# STM32Fx.net
KiCad netlist of a schematic drawn in Altium Designer
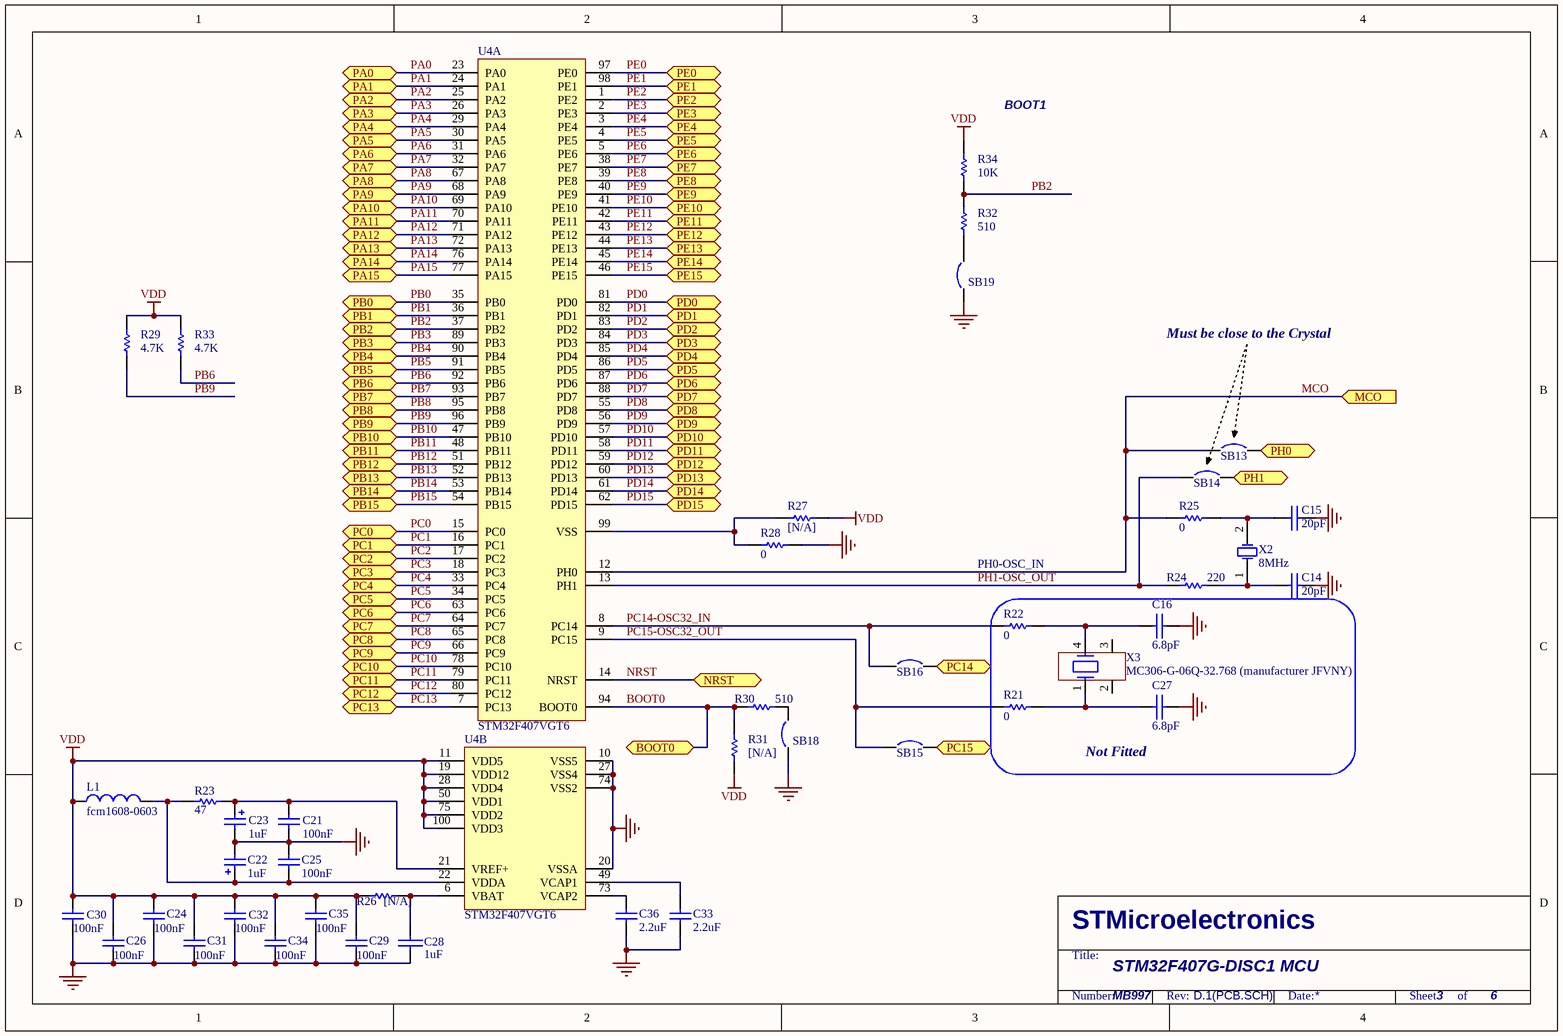
[diagram p0: STM32Fx.SchDoc]

(export (version "E")
  (design (tool "Eeschema 10.0.6"))
  (components
    (comp (ref "C14")
      (value "20pF")
      (footprint "0603C")
      (description "Capacitor")
      (libsource (lib "") (part "CAP_1"))
    )
    (comp (ref "C15")
      (value "20pF")
      (footprint "0603C")
      (description "Capacitor")
      (libsource (lib "") (part "CAP_1"))
    )
    (comp (ref "C16")
      (value "6.8pF")
      (footprint "0603C")
      (description "Capacitor")
      (libsource (lib "*") (part "CAP"))
    )
    (comp (ref "C21")
      (value "100nF")
      (footprint "0603C")
      (description "Capacitor")
      (fields (field (name "PUBLISHER") "Altium Limited"))
      (libsource (lib "MB915_1") (part "Cap"))
    )
    (comp (ref "C22")
      (value "1uF")
      (footprint "CASE-AA")
      (description "Polarized Capacitor (Radial)")
      (fields (field (name "PUBLISHER") "Altium Limited"))
      (libsource (lib "Miscellaneous Devices") (part "Cap Pol1"))
    )
    (comp (ref "C23")
      (value "1uF")
      (footprint "CASE-AA")
      (description "Polarized Capacitor (Radial)")
      (fields (field (name "PUBLISHER") "Altium Limited"))
      (libsource (lib "Miscellaneous Devices") (part "Cap Pol1"))
    )
    (comp (ref "C24")
      (value "100nF")
      (footprint "0603C")
      (description "Capacitor")
      (fields (field (name "PUBLISHER") "Altium Limited"))
      (libsource (lib "MB915_1") (part "Cap"))
    )
    (comp (ref "C25")
      (value "100nF")
      (footprint "0603C")
      (description "Capacitor")
      (fields (field (name "PUBLISHER") "Altium Limited"))
      (libsource (lib "MB915_1") (part "Cap"))
    )
    (comp (ref "C26")
      (value "100nF")
      (footprint "0603C")
      (description "Capacitor")
      (fields (field (name "PUBLISHER") "Altium Limited"))
      (libsource (lib "MB915_1") (part "Cap"))
    )
    (comp (ref "C27")
      (value "6.8pF")
      (footprint "0603C")
      (description "Capacitor")
      (libsource (lib "*") (part "CAP"))
    )
    (comp (ref "C28")
      (value "1uF")
      (footprint "0603C")
      (description "Capacitor")
      (libsource (lib "") (part "CAP_1"))
    )
    (comp (ref "C29")
      (value "100nF")
      (footprint "0603C")
      (description "Capacitor")
      (fields (field (name "PUBLISHER") "Altium Limited"))
      (libsource (lib "MB915_1") (part "Cap"))
    )
    (comp (ref "C30")
      (value "100nF")
      (footprint "0603C")
      (description "Capacitor")
      (fields (field (name "PUBLISHER") "Altium Limited"))
      (libsource (lib "MB915_1") (part "Cap"))
    )
    (comp (ref "C31")
      (value "100nF")
      (footprint "0603C")
      (description "Capacitor")
      (fields (field (name "PUBLISHER") "Altium Limited"))
      (libsource (lib "MB915_1") (part "Cap"))
    )
    (comp (ref "C32")
      (value "100nF")
      (footprint "0603C")
      (description "Capacitor")
      (fields (field (name "PUBLISHER") "Altium Limited"))
      (libsource (lib "MB915_1") (part "Cap"))
    )
    (comp (ref "C33")
      (value "2.2uF")
      (footprint "CASE-A")
      (description "Low ESR Ceramic Capacitor (X7R)")
      (fields (field (name "PUBLISHER") "Altium Limited"))
      (libsource (lib "MB997") (part "Cap Low ESR"))
    )
    (comp (ref "C34")
      (value "100nF")
      (footprint "0603C")
      (description "Capacitor")
      (fields (field (name "PUBLISHER") "Altium Limited"))
      (libsource (lib "MB915_1") (part "Cap"))
    )
    (comp (ref "C35")
      (value "100nF")
      (footprint "0603C")
      (description "Capacitor")
      (fields (field (name "PUBLISHER") "Altium Limited"))
      (libsource (lib "MB915_1") (part "Cap"))
    )
    (comp (ref "C36")
      (value "2.2uF")
      (footprint "CASE-A")
      (description "Low ESR Ceramic Capacitor (X7R)")
      (fields (field (name "PUBLISHER") "Altium Limited"))
      (libsource (lib "MB997") (part "Cap Low ESR"))
    )
    (comp (ref "L1")
      (value "fcm1608-0603")
      (footprint "0603L")
      (description "Inductor")
      (fields (field (name "PUBLISHER") "Altium Limited"))
      (libsource (lib "Miscellaneous Devices") (part "Inductor"))
    )
    (comp (ref "R21")
      (value "0")
      (footprint "0603R")
      (description "Resistor")
      (fields (field (name "PUBLISHER") "Altium Limited"))
      (libsource (lib "Miscellaneous Devices") (part "Res1"))
    )
    (comp (ref "R22")
      (value "0")
      (footprint "0603R")
      (description "Resistor")
      (fields (field (name "PUBLISHER") "Altium Limited"))
      (libsource (lib "Miscellaneous Devices") (part "Res1"))
    )
    (comp (ref "R23")
      (value "47")
      (footprint "0603R")
      (description "Resistor")
      (fields (field (name "PUBLISHER") "Altium Limited"))
      (libsource (lib "Miscellaneous Devices") (part "Res1"))
    )
    (comp (ref "R24")
      (value "220")
      (footprint "0603R")
      (description "Resistor")
      (fields (field (name "PUBLISHER") "Altium Limited"))
      (libsource (lib "Miscellaneous Devices") (part "Res1"))
    )
    (comp (ref "R25")
      (value "0")
      (footprint "0603R")
      (description "Resistor")
      (fields (field (name "PUBLISHER") "Altium Limited"))
      (libsource (lib "Miscellaneous Devices") (part "Res1"))
    )
    (comp (ref "R26")
      (value "[N/A]")
      (footprint "0603R")
      (description "Resistor")
      (fields (field (name "PUBLISHER") "Altium Limited"))
      (libsource (lib "Miscellaneous Devices") (part "res1"))
    )
    (comp (ref "R27")
      (value "[N/A]")
      (footprint "0603R")
      (description "Resistor")
      (fields (field (name "PUBLISHER") "Altium Limited"))
      (libsource (lib "Miscellaneous Devices") (part "Res1"))
    )
    (comp (ref "R28")
      (value "0")
      (footprint "0603R")
      (description "Resistor")
      (fields (field (name "PUBLISHER") "Altium Limited"))
      (libsource (lib "Miscellaneous Devices") (part "Res1"))
    )
    (comp (ref "R29")
      (value "4.7K")
      (footprint "0402R")
      (description "Resistor")
      (fields (field (name "PUBLISHER") "Altium Limited"))
      (libsource (lib "Miscellaneous Devices") (part "res1"))
    )
    (comp (ref "R30")
      (value "510")
      (footprint "0603R")
      (description "Resistor")
      (fields (field (name "PUBLISHER") "Altium Limited"))
      (libsource (lib "Miscellaneous Devices") (part "Res1"))
    )
    (comp (ref "R31")
      (value "[N/A]")
      (footprint "0402R")
      (description "Resistor")
      (fields (field (name "PUBLISHER") "Altium Limited"))
      (libsource (lib "Miscellaneous Devices") (part "res1"))
    )
    (comp (ref "R32")
      (value "510")
      (footprint "0603R")
      (description "Resistor")
      (fields (field (name "PUBLISHER") "Altium Limited"))
      (libsource (lib "Miscellaneous Devices") (part "res1"))
    )
    (comp (ref "R33")
      (value "4.7K")
      (footprint "0402R")
      (description "Resistor")
      (fields (field (name "PUBLISHER") "Altium Limited"))
      (libsource (lib "Miscellaneous Devices") (part "res1"))
    )
    (comp (ref "R34")
      (value "10K")
      (footprint "0402R")
      (description "Resistor")
      (fields (field (name "PUBLISHER") "Altium Limited"))
      (libsource (lib "Miscellaneous Devices") (part "res1"))
    )
    (comp (ref "SB13")
      (value "Circuit Breaker")
      (footprint "JP2_SMD")
      (fields (field (name "PUBLISHER") "Altium Limited"))
      (libsource (lib "MB915") (part "Circuit Breaker"))
    )
    (comp (ref "SB14")
      (value "Circuit Breaker")
      (footprint "JP2_SMD")
      (fields (field (name "PUBLISHER") "Altium Limited"))
      (libsource (lib "MB915") (part "Circuit Breaker"))
    )
    (comp (ref "SB15")
      (value "Circuit Breaker")
      (footprint "JP2_SMD")
      (fields (field (name "PUBLISHER") "Altium Limited"))
      (libsource (lib "MB915") (part "Circuit Breaker"))
    )
    (comp (ref "SB16")
      (value "Circuit Breaker")
      (footprint "JP2_SMD")
      (fields (field (name "PUBLISHER") "Altium Limited"))
      (libsource (lib "MB915") (part "Circuit Breaker"))
    )
    (comp (ref "SB18")
      (value "Circuit Breaker")
      (footprint "JP2_SMD")
      (fields (field (name "PUBLISHER") "Altium Limited"))
      (libsource (lib "MB915") (part "Circuit Breaker"))
    )
    (comp (ref "SB19")
      (value "Circuit Breaker")
      (footprint "JP2_SMD")
      (fields (field (name "PUBLISHER") "Altium Limited"))
      (libsource (lib "MB915") (part "Circuit Breaker"))
    )
    (comp (ref "U4")
      (value "STM32F407VGT6")
      (footprint "TQFP100")
      (description "STM32 Manta (STM32F407VGT6)")
      (libsource (lib "MCD_TOOLS") (part "STM32F407VGT6"))
    )
    (comp (ref "X2")
      (value "8MHz")
      (footprint "XTAL1")
      (description "Crystal Oscillator")
      (fields (field (name "PUBLISHER") "Altium Limited"))
      (libsource (lib "MB963_1") (part "XTAL"))
    )
    (comp (ref "X3")
      (value "MC306-G-06Q-32.768 (manufacturer JFVNY)")
      (footprint "MC306-CRYSTAL")
      (libsource (lib "*") (part "MC306"))
    )
  )
  (nets
    (net (code "1") (name "/BOOT0") (class "Default")
      (node (ref "R30") (pin "2") (pinfunction "2_2") (pintype "passive"))
      (node (ref "R31") (pin "1") (pinfunction "1_1") (pintype "passive"))
      (node (ref "U4") (pin "94") (pinfunction "BOOT0_94") (pintype "passive"))
    )
    (net (code "2") (name "/MCO") (class "Default")
      (node (ref "R25") (pin "1") (pinfunction "1_1") (pintype "passive"))
      (node (ref "SB13") (pin "1") (pinfunction "1_1") (pintype "passive"))
      (node (ref "U4") (pin "12") (pinfunction "PH0_12") (pintype "passive"))
    )
    (net (code "3") (name "/NRST") (class "Default")
      (node (ref "U4") (pin "14") (pinfunction "NRST_14") (pintype "passive"))
    )
    (net (code "4") (name "/PA0") (class "Default")
      (node (ref "U4") (pin "23") (pinfunction "PA0_23") (pintype "passive"))
    )
    (net (code "5") (name "/PA1") (class "Default")
      (node (ref "U4") (pin "24") (pinfunction "PA1_24") (pintype "passive"))
    )
    (net (code "6") (name "/PA2") (class "Default")
      (node (ref "U4") (pin "25") (pinfunction "PA2_25") (pintype "passive"))
    )
    (net (code "7") (name "/PA3") (class "Default")
      (node (ref "U4") (pin "26") (pinfunction "PA3_26") (pintype "passive"))
    )
    (net (code "8") (name "/PA4") (class "Default")
      (node (ref "U4") (pin "29") (pinfunction "PA4_29") (pintype "passive"))
    )
    (net (code "9") (name "/PA5") (class "Default")
      (node (ref "U4") (pin "30") (pinfunction "PA5_30") (pintype "passive"))
    )
    (net (code "10") (name "/PA6") (class "Default")
      (node (ref "U4") (pin "31") (pinfunction "PA6_31") (pintype "passive"))
    )
    (net (code "11") (name "/PA7") (class "Default")
      (node (ref "U4") (pin "32") (pinfunction "PA7_32") (pintype "passive"))
    )
    (net (code "12") (name "/PA8") (class "Default")
      (node (ref "U4") (pin "67") (pinfunction "PA8_67") (pintype "passive"))
    )
    (net (code "13") (name "/PA9") (class "Default")
      (node (ref "U4") (pin "68") (pinfunction "PA9_68") (pintype "passive"))
    )
    (net (code "14") (name "/PA10") (class "Default")
      (node (ref "U4") (pin "69") (pinfunction "PA10_69") (pintype "passive"))
    )
    (net (code "15") (name "/PA11") (class "Default")
      (node (ref "U4") (pin "70") (pinfunction "PA11_70") (pintype "passive"))
    )
    (net (code "16") (name "/PA12") (class "Default")
      (node (ref "U4") (pin "71") (pinfunction "PA12_71") (pintype "passive"))
    )
    (net (code "17") (name "/PA13") (class "Default")
      (node (ref "U4") (pin "72") (pinfunction "PA13_72") (pintype "passive"))
    )
    (net (code "18") (name "/PA14") (class "Default")
      (node (ref "U4") (pin "76") (pinfunction "PA14_76") (pintype "passive"))
    )
    (net (code "19") (name "/PA15") (class "Default")
      (node (ref "U4") (pin "77") (pinfunction "PA15_77") (pintype "passive"))
    )
    (net (code "20") (name "/PB0") (class "Default")
      (node (ref "U4") (pin "35") (pinfunction "PB0_35") (pintype "passive"))
    )
    (net (code "21") (name "/PB1") (class "Default")
      (node (ref "U4") (pin "36") (pinfunction "PB1_36") (pintype "passive"))
    )
    (net (code "22") (name "/PB2") (class "Default")
      (node (ref "R32") (pin "1") (pinfunction "1_1") (pintype "passive"))
      (node (ref "R34") (pin "2") (pinfunction "2_2") (pintype "passive"))
      (node (ref "U4") (pin "37") (pinfunction "PB2_37") (pintype "passive"))
    )
    (net (code "23") (name "/PB3") (class "Default")
      (node (ref "U4") (pin "89") (pinfunction "PB3_89") (pintype "passive"))
    )
    (net (code "24") (name "/PB4") (class "Default")
      (node (ref "U4") (pin "90") (pinfunction "PB4_90") (pintype "passive"))
    )
    (net (code "25") (name "/PB5") (class "Default")
      (node (ref "U4") (pin "91") (pinfunction "PB5_91") (pintype "passive"))
    )
    (net (code "26") (name "/PB6") (class "Default")
      (node (ref "R33") (pin "2") (pinfunction "2_2") (pintype "passive"))
      (node (ref "U4") (pin "92") (pinfunction "PB6_92") (pintype "passive"))
    )
    (net (code "27") (name "/PB7") (class "Default")
      (node (ref "U4") (pin "93") (pinfunction "PB7_93") (pintype "passive"))
    )
    (net (code "28") (name "/PB8") (class "Default")
      (node (ref "U4") (pin "95") (pinfunction "PB8_95") (pintype "passive"))
    )
    (net (code "29") (name "/PB9") (class "Default")
      (node (ref "R29") (pin "2") (pinfunction "2_2") (pintype "passive"))
      (node (ref "U4") (pin "96") (pinfunction "PB9_96") (pintype "passive"))
    )
    (net (code "30") (name "/PB10") (class "Default")
      (node (ref "U4") (pin "47") (pinfunction "PB10_47") (pintype "passive"))
    )
    (net (code "31") (name "/PB11") (class "Default")
      (node (ref "U4") (pin "48") (pinfunction "PB11_48") (pintype "passive"))
    )
    (net (code "32") (name "/PB12") (class "Default")
      (node (ref "U4") (pin "51") (pinfunction "PB12_51") (pintype "passive"))
    )
    (net (code "33") (name "/PB13") (class "Default")
      (node (ref "U4") (pin "52") (pinfunction "PB13_52") (pintype "passive"))
    )
    (net (code "34") (name "/PB14") (class "Default")
      (node (ref "U4") (pin "53") (pinfunction "PB14_53") (pintype "passive"))
    )
    (net (code "35") (name "/PB15") (class "Default")
      (node (ref "U4") (pin "54") (pinfunction "PB15_54") (pintype "passive"))
    )
    (net (code "36") (name "/PC0") (class "Default")
      (node (ref "U4") (pin "15") (pinfunction "PC0_15") (pintype "passive"))
    )
    (net (code "37") (name "/PC1") (class "Default")
      (node (ref "U4") (pin "16") (pinfunction "PC1_16") (pintype "passive"))
    )
    (net (code "38") (name "/PC2") (class "Default")
      (node (ref "U4") (pin "17") (pinfunction "PC2_17") (pintype "passive"))
    )
    (net (code "39") (name "/PC3") (class "Default")
      (node (ref "U4") (pin "18") (pinfunction "PC3_18") (pintype "passive"))
    )
    (net (code "40") (name "/PC4") (class "Default")
      (node (ref "U4") (pin "33") (pinfunction "PC4_33") (pintype "passive"))
    )
    (net (code "41") (name "/PC5") (class "Default")
      (node (ref "U4") (pin "34") (pinfunction "PC5_34") (pintype "passive"))
    )
    (net (code "42") (name "/PC6") (class "Default")
      (node (ref "U4") (pin "63") (pinfunction "PC6_63") (pintype "passive"))
    )
    (net (code "43") (name "/PC7") (class "Default")
      (node (ref "U4") (pin "64") (pinfunction "PC7_64") (pintype "passive"))
    )
    (net (code "44") (name "/PC8") (class "Default")
      (node (ref "U4") (pin "65") (pinfunction "PC8_65") (pintype "passive"))
    )
    (net (code "45") (name "/PC9") (class "Default")
      (node (ref "U4") (pin "66") (pinfunction "PC9_66") (pintype "passive"))
    )
    (net (code "46") (name "/PC10") (class "Default")
      (node (ref "U4") (pin "78") (pinfunction "PC10_78") (pintype "passive"))
    )
    (net (code "47") (name "/PC11") (class "Default")
      (node (ref "U4") (pin "79") (pinfunction "PC11_79") (pintype "passive"))
    )
    (net (code "48") (name "/PC12") (class "Default")
      (node (ref "U4") (pin "80") (pinfunction "PC12_80") (pintype "passive"))
    )
    (net (code "49") (name "/PC13") (class "Default")
      (node (ref "U4") (pin "7") (pinfunction "PC13_7") (pintype "passive"))
    )
    (net (code "50") (name "/PC14") (class "Default")
      (node (ref "SB16") (pin "2") (pinfunction "2_2") (pintype "passive"))
    )
    (net (code "51") (name "/PC14-OSC32_IN") (class "Default")
      (node (ref "R22") (pin "1") (pinfunction "1_1") (pintype "passive"))
      (node (ref "SB16") (pin "1") (pinfunction "1_1") (pintype "passive"))
      (node (ref "U4") (pin "8") (pinfunction "PC14_8") (pintype "passive"))
    )
    (net (code "52") (name "/PC15") (class "Default")
      (node (ref "SB15") (pin "2") (pinfunction "2_2") (pintype "passive"))
    )
    (net (code "53") (name "/PC15-OSC32_OUT") (class "Default")
      (node (ref "R21") (pin "1") (pinfunction "1_1") (pintype "passive"))
      (node (ref "SB15") (pin "1") (pinfunction "1_1") (pintype "passive"))
      (node (ref "U4") (pin "9") (pinfunction "PC15_9") (pintype "passive"))
    )
    (net (code "54") (name "/PD0") (class "Default")
      (node (ref "U4") (pin "81") (pinfunction "PD0_81") (pintype "passive"))
    )
    (net (code "55") (name "/PD1") (class "Default")
      (node (ref "U4") (pin "82") (pinfunction "PD1_82") (pintype "passive"))
    )
    (net (code "56") (name "/PD2") (class "Default")
      (node (ref "U4") (pin "83") (pinfunction "PD2_83") (pintype "passive"))
    )
    (net (code "57") (name "/PD3") (class "Default")
      (node (ref "U4") (pin "84") (pinfunction "PD3_84") (pintype "passive"))
    )
    (net (code "58") (name "/PD4") (class "Default")
      (node (ref "U4") (pin "85") (pinfunction "PD4_85") (pintype "passive"))
    )
    (net (code "59") (name "/PD5") (class "Default")
      (node (ref "U4") (pin "86") (pinfunction "PD5_86") (pintype "passive"))
    )
    (net (code "60") (name "/PD6") (class "Default")
      (node (ref "U4") (pin "87") (pinfunction "PD6_87") (pintype "passive"))
    )
    (net (code "61") (name "/PD7") (class "Default")
      (node (ref "U4") (pin "88") (pinfunction "PD7_88") (pintype "passive"))
    )
    (net (code "62") (name "/PD8") (class "Default")
      (node (ref "U4") (pin "55") (pinfunction "PD8_55") (pintype "passive"))
    )
    (net (code "63") (name "/PD9") (class "Default")
      (node (ref "U4") (pin "56") (pinfunction "PD9_56") (pintype "passive"))
    )
    (net (code "64") (name "/PD10") (class "Default")
      (node (ref "U4") (pin "57") (pinfunction "PD10_57") (pintype "passive"))
    )
    (net (code "65") (name "/PD11") (class "Default")
      (node (ref "U4") (pin "58") (pinfunction "PD11_58") (pintype "passive"))
    )
    (net (code "66") (name "/PD12") (class "Default")
      (node (ref "U4") (pin "59") (pinfunction "PD12_59") (pintype "passive"))
    )
    (net (code "67") (name "/PD13") (class "Default")
      (node (ref "U4") (pin "60") (pinfunction "PD13_60") (pintype "passive"))
    )
    (net (code "68") (name "/PD14") (class "Default")
      (node (ref "U4") (pin "61") (pinfunction "PD14_61") (pintype "passive"))
    )
    (net (code "69") (name "/PD15") (class "Default")
      (node (ref "U4") (pin "62") (pinfunction "PD15_62") (pintype "passive"))
    )
    (net (code "70") (name "/PE0") (class "Default")
      (node (ref "U4") (pin "97") (pinfunction "PE0_97") (pintype "passive"))
    )
    (net (code "71") (name "/PE1") (class "Default")
      (node (ref "U4") (pin "98") (pinfunction "PE1_98") (pintype "passive"))
    )
    (net (code "72") (name "/PE2") (class "Default")
      (node (ref "U4") (pin "1") (pinfunction "PE2_1") (pintype "passive"))
    )
    (net (code "73") (name "/PE3") (class "Default")
      (node (ref "U4") (pin "2") (pinfunction "PE3_2") (pintype "passive"))
    )
    (net (code "74") (name "/PE4") (class "Default")
      (node (ref "U4") (pin "3") (pinfunction "PE4_3") (pintype "passive"))
    )
    (net (code "75") (name "/PE5") (class "Default")
      (node (ref "U4") (pin "4") (pinfunction "PE5_4") (pintype "passive"))
    )
    (net (code "76") (name "/PE6") (class "Default")
      (node (ref "U4") (pin "5") (pinfunction "PE6_5") (pintype "passive"))
    )
    (net (code "77") (name "/PE7") (class "Default")
      (node (ref "U4") (pin "38") (pinfunction "PE7_38") (pintype "passive"))
    )
    (net (code "78") (name "/PE8") (class "Default")
      (node (ref "U4") (pin "39") (pinfunction "PE8_39") (pintype "passive"))
    )
    (net (code "79") (name "/PE9") (class "Default")
      (node (ref "U4") (pin "40") (pinfunction "PE9_40") (pintype "passive"))
    )
    (net (code "80") (name "/PE10") (class "Default")
      (node (ref "U4") (pin "41") (pinfunction "PE10_41") (pintype "passive"))
    )
    (net (code "81") (name "/PE11") (class "Default")
      (node (ref "U4") (pin "42") (pinfunction "PE11_42") (pintype "passive"))
    )
    (net (code "82") (name "/PE12") (class "Default")
      (node (ref "U4") (pin "43") (pinfunction "PE12_43") (pintype "passive"))
    )
    (net (code "83") (name "/PE13") (class "Default")
      (node (ref "U4") (pin "44") (pinfunction "PE13_44") (pintype "passive"))
    )
    (net (code "84") (name "/PE14") (class "Default")
      (node (ref "U4") (pin "45") (pinfunction "PE14_45") (pintype "passive"))
    )
    (net (code "85") (name "/PE15") (class "Default")
      (node (ref "U4") (pin "46") (pinfunction "PE15_46") (pintype "passive"))
    )
    (net (code "86") (name "/PH0") (class "Default")
      (node (ref "SB13") (pin "2") (pinfunction "2_2") (pintype "passive"))
    )
    (net (code "87") (name "/PH1") (class "Default")
      (node (ref "SB14") (pin "2") (pinfunction "2_2") (pintype "passive"))
    )
    (net (code "88") (name "/PH1-OSC_OUT") (class "Default")
      (node (ref "R24") (pin "2") (pinfunction "2_2") (pintype "passive"))
      (node (ref "SB14") (pin "1") (pinfunction "1_1") (pintype "passive"))
      (node (ref "U4") (pin "13") (pinfunction "PH1_13") (pintype "passive"))
    )
    (net (code "89") (name "GND") (class "Default")
      (node (ref "C14") (pin "1") (pinfunction "1_1") (pintype "passive"))
      (node (ref "C15") (pin "1") (pinfunction "1_1") (pintype "passive"))
      (node (ref "C16") (pin "2") (pinfunction "2_2") (pintype "passive"))
      (node (ref "C21") (pin "1") (pinfunction "1_1") (pintype "passive"))
      (node (ref "C22") (pin "2") (pinfunction "2_2") (pintype "passive"))
      (node (ref "C23") (pin "2") (pinfunction "2_2") (pintype "passive"))
      (node (ref "C24") (pin "2") (pinfunction "2_2") (pintype "passive"))
      (node (ref "C25") (pin "1") (pinfunction "1_1") (pintype "passive"))
      (node (ref "C26") (pin "1") (pinfunction "1_1") (pintype "passive"))
      (node (ref "C27") (pin "2") (pinfunction "2_2") (pintype "passive"))
      (node (ref "C28") (pin "2") (pinfunction "2_2") (pintype "passive"))
      (node (ref "C29") (pin "1") (pinfunction "1_1") (pintype "passive"))
      (node (ref "C30") (pin "1") (pinfunction "1_1") (pintype "passive"))
      (node (ref "C31") (pin "1") (pinfunction "1_1") (pintype "passive"))
      (node (ref "C32") (pin "1") (pinfunction "1_1") (pintype "passive"))
      (node (ref "C33") (pin "2") (pinfunction "2_2") (pintype "passive"))
      (node (ref "C34") (pin "1") (pinfunction "1_1") (pintype "passive"))
      (node (ref "C35") (pin "2") (pinfunction "2_2") (pintype "passive"))
      (node (ref "C36") (pin "2") (pinfunction "2_2") (pintype "passive"))
      (node (ref "R28") (pin "2") (pinfunction "2_2") (pintype "passive"))
      (node (ref "SB18") (pin "1") (pinfunction "1_1") (pintype "passive"))
      (node (ref "SB19") (pin "1") (pinfunction "1_1") (pintype "passive"))
      (node (ref "U4") (pin "10") (pinfunction "VSS5_10") (pintype "passive"))
      (node (ref "U4") (pin "20") (pinfunction "VSSA_20") (pintype "passive"))
      (node (ref "U4") (pin "27") (pinfunction "VSS4_27") (pintype "passive"))
      (node (ref "U4") (pin "74") (pinfunction "VSS2_74") (pintype "passive"))
    )
    (net (code "90") (name "Net-(C16-Pad1)") (class "Default")
      (node (ref "C16") (pin "1") (pinfunction "1_1") (pintype "passive"))
      (node (ref "R22") (pin "2") (pinfunction "2_2") (pintype "passive"))
      (node (ref "X3") (pin "4") (pinfunction "4_4") (pintype "passive"))
    )
    (net (code "91") (name "Net-(C27-Pad1)") (class "Default")
      (node (ref "C27") (pin "1") (pinfunction "1_1") (pintype "passive"))
      (node (ref "R21") (pin "2") (pinfunction "2_2") (pintype "passive"))
      (node (ref "X3") (pin "1") (pinfunction "1_1") (pintype "passive"))
    )
    (net (code "92") (name "Net-(R30-Pad1)") (class "Default")
      (node (ref "R30") (pin "1") (pinfunction "1_1") (pintype "passive"))
      (node (ref "SB18") (pin "2") (pinfunction "2_2") (pintype "passive"))
    )
    (net (code "93") (name "Net-(R32-Pad2)") (class "Default")
      (node (ref "R32") (pin "2") (pinfunction "2_2") (pintype "passive"))
      (node (ref "SB19") (pin "2") (pinfunction "2_2") (pintype "passive"))
    )
    (net (code "94") (name "Net-(U4A-VSS)") (class "Default")
      (node (ref "R27") (pin "1") (pinfunction "1_1") (pintype "passive"))
      (node (ref "R28") (pin "1") (pinfunction "1_1") (pintype "passive"))
      (node (ref "U4") (pin "99") (pinfunction "VSS_99") (pintype "passive"))
    )
    (net (code "95") (name "Net-(U4B-VBAT)") (class "Default")
      (node (ref "C28") (pin "1") (pinfunction "1_1") (pintype "passive"))
      (node (ref "R26") (pin "2") (pinfunction "2_2") (pintype "passive"))
      (node (ref "U4") (pin "6") (pinfunction "VBAT_6") (pintype "passive"))
    )
    (net (code "96") (name "Net-(U4B-VCAP1)") (class "Default")
      (node (ref "C33") (pin "1") (pinfunction "1_1") (pintype "passive"))
      (node (ref "U4") (pin "49") (pinfunction "VCAP1_49") (pintype "passive"))
    )
    (net (code "97") (name "Net-(U4B-VCAP2)") (class "Default")
      (node (ref "C36") (pin "1") (pinfunction "1_1") (pintype "passive"))
      (node (ref "U4") (pin "73") (pinfunction "VCAP2_73") (pintype "passive"))
    )
    (net (code "98") (name "Net-(U4B-VDDA)") (class "Default")
      (node (ref "C22") (pin "1") (pinfunction "1_1") (pintype "passive"))
      (node (ref "C25") (pin "2") (pinfunction "2_2") (pintype "passive"))
      (node (ref "L1") (pin "2") (pinfunction "2_2") (pintype "passive"))
      (node (ref "R23") (pin "2") (pinfunction "2_2") (pintype "passive"))
      (node (ref "U4") (pin "22") (pinfunction "VDDA_22") (pintype "passive"))
    )
    (net (code "99") (name "Net-(U4B-VREF+)") (class "Default")
      (node (ref "C21") (pin "2") (pinfunction "2_2") (pintype "passive"))
      (node (ref "C23") (pin "1") (pinfunction "1_1") (pintype "passive"))
      (node (ref "R23") (pin "1") (pinfunction "1_1") (pintype "passive"))
      (node (ref "U4") (pin "21") (pinfunction "VREF+_21") (pintype "passive"))
    )
    (net (code "100") (name "Net-(X2-OSC1)") (class "Default")
      (node (ref "C14") (pin "2") (pinfunction "2_2") (pintype "passive"))
      (node (ref "R24") (pin "1") (pinfunction "1_1") (pintype "passive"))
      (node (ref "X2") (pin "1") (pinfunction "OSC1_1") (pintype "passive"))
    )
    (net (code "101") (name "Net-(X2-OSC2)") (class "Default")
      (node (ref "C15") (pin "2") (pinfunction "2_2") (pintype "passive"))
      (node (ref "R25") (pin "2") (pinfunction "2_2") (pintype "passive"))
      (node (ref "X2") (pin "2") (pinfunction "OSC2_2") (pintype "passive"))
    )
    (net (code "102") (name "VDD") (class "Default")
      (node (ref "C24") (pin "1") (pinfunction "1_1") (pintype "passive"))
      (node (ref "C26") (pin "2") (pinfunction "2_2") (pintype "passive"))
      (node (ref "C29") (pin "2") (pinfunction "2_2") (pintype "passive"))
      (node (ref "C30") (pin "2") (pinfunction "2_2") (pintype "passive"))
      (node (ref "C31") (pin "2") (pinfunction "2_2") (pintype "passive"))
      (node (ref "C32") (pin "2") (pinfunction "2_2") (pintype "passive"))
      (node (ref "C34") (pin "2") (pinfunction "2_2") (pintype "passive"))
      (node (ref "C35") (pin "1") (pinfunction "1_1") (pintype "passive"))
      (node (ref "L1") (pin "1") (pinfunction "1_1") (pintype "passive"))
      (node (ref "R26") (pin "1") (pinfunction "1_1") (pintype "passive"))
      (node (ref "R27") (pin "2") (pinfunction "2_2") (pintype "passive"))
      (node (ref "R29") (pin "1") (pinfunction "1_1") (pintype "passive"))
      (node (ref "R31") (pin "2") (pinfunction "2_2") (pintype "passive"))
      (node (ref "R33") (pin "1") (pinfunction "1_1") (pintype "passive"))
      (node (ref "R34") (pin "1") (pinfunction "1_1") (pintype "passive"))
      (node (ref "U4") (pin "100") (pinfunction "VDD3_100") (pintype "passive"))
      (node (ref "U4") (pin "11") (pinfunction "VDD5_11") (pintype "passive"))
      (node (ref "U4") (pin "19") (pinfunction "VDD12_19") (pintype "passive"))
      (node (ref "U4") (pin "28") (pinfunction "VDD4_28") (pintype "passive"))
      (node (ref "U4") (pin "50") (pinfunction "VDD1_50") (pintype "passive"))
      (node (ref "U4") (pin "75") (pinfunction "VDD2_75") (pintype "passive"))
    )
    (net (code "103") (name "unconnected-(X3-Pad2)") (class "Default")
      (node (ref "X3") (pin "2") (pinfunction "2_2") (pintype "passive"))
    )
    (net (code "104") (name "unconnected-(X3-Pad3)") (class "Default")
      (node (ref "X3") (pin "3") (pinfunction "3_3") (pintype "passive"))
    )
  )
)
